# untitled.net
KiCad netlist of a schematic drawn in EAGLE
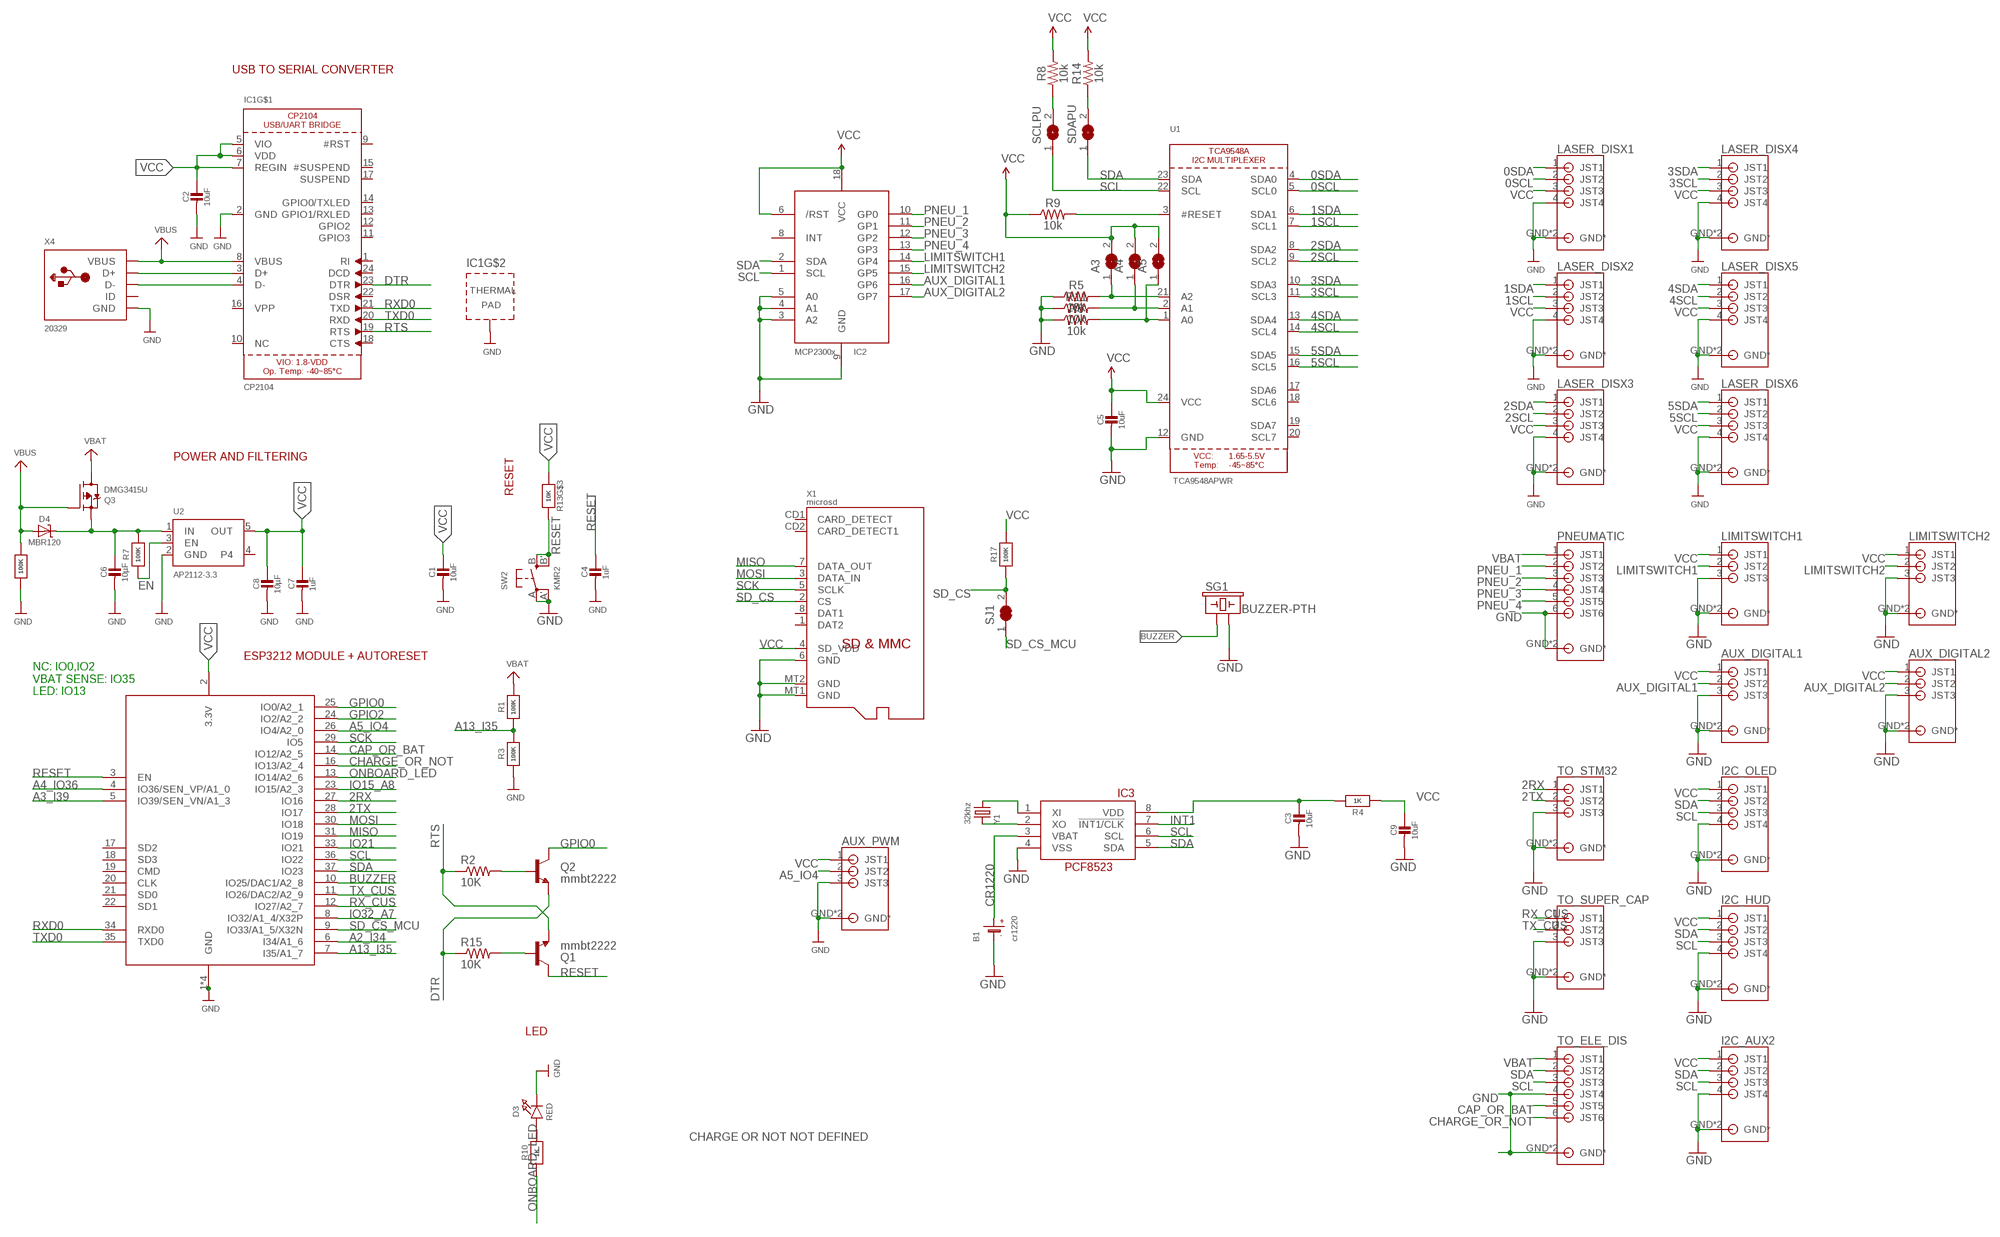
[diagram p0: schematic, sheet 1]

(export (version "E")
  (design (tool "Eeschema 10.0.6"))
  (components
    (comp (ref "A3")
      (value "SOLDERJUMPER")
      (footprint "eagle-import:SOLDERJUMPER_ARROW_NOPASTE")
      (libsource (lib "eagle-import") (part "SOLDERJUMPER"))
    )
    (comp (ref "A4")
      (value "SOLDERJUMPER")
      (footprint "eagle-import:SOLDERJUMPER_ARROW_NOPASTE")
      (libsource (lib "eagle-import") (part "SOLDERJUMPER"))
    )
    (comp (ref "A5")
      (value "SOLDERJUMPER")
      (footprint "eagle-import:SOLDERJUMPER_ARROW_NOPASTE")
      (libsource (lib "eagle-import") (part "SOLDERJUMPER"))
    )
    (comp (ref "AUX_DIGITAL1")
      (value "S3B-PH-SM4_TB")
      (footprint "eagle-import:S3B-PH-SM4_TB")
      (libsource (lib "eagle-import") (part "S3B-PH-SM4_TB"))
    )
    (comp (ref "AUX_DIGITAL2")
      (value "S3B-PH-SM4_TB")
      (footprint "eagle-import:S3B-PH-SM4_TB")
      (libsource (lib "eagle-import") (part "S3B-PH-SM4_TB"))
    )
    (comp (ref "AUX_PWM")
      (value "S3B-PH-SM4_TB")
      (footprint "eagle-import:S3B-PH-SM4_TB")
      (libsource (lib "eagle-import") (part "S3B-PH-SM4_TB"))
    )
    (comp (ref "B1")
      (value "cr1220")
      (footprint "eagle-import:CR1220-2")
      (libsource (lib "eagle-import") (part "BATTERYCR1220_2"))
    )
    (comp (ref "C1")
      (value "10uF")
      (footprint "eagle-import:0805-NO")
      (libsource (lib "eagle-import") (part "CAP_CERAMIC0805-NOOUTLINE"))
    )
    (comp (ref "C2")
      (value "10uF")
      (footprint "eagle-import:0805-NO")
      (libsource (lib "eagle-import") (part "CAP_CERAMIC0805-NOOUTLINE"))
    )
    (comp (ref "C3")
      (value "10uF")
      (footprint "eagle-import:0805-NO")
      (libsource (lib "eagle-import") (part "CAP_CERAMIC0805-NOOUTLINE"))
    )
    (comp (ref "C4")
      (value "1uF")
      (footprint "eagle-import:0603-NO")
      (libsource (lib "eagle-import") (part "CAP_CERAMIC0603_NO"))
    )
    (comp (ref "C5")
      (value "10uF")
      (footprint "eagle-import:0805-NO")
      (libsource (lib "eagle-import") (part "CAP_CERAMIC0805-NOOUTLINE"))
    )
    (comp (ref "C6")
      (value "10µF")
      (footprint "eagle-import:0805-NO")
      (libsource (lib "eagle-import") (part "CAP_CERAMIC0805-NOOUTLINE"))
    )
    (comp (ref "C7")
      (value "1uF")
      (footprint "eagle-import:0603-NO")
      (libsource (lib "eagle-import") (part "CAP_CERAMIC0603_NO"))
    )
    (comp (ref "C8")
      (value "10µF")
      (footprint "eagle-import:0805-NO")
      (libsource (lib "eagle-import") (part "CAP_CERAMIC0805-NOOUTLINE"))
    )
    (comp (ref "C9")
      (value "10uF")
      (footprint "eagle-import:0805-NO")
      (libsource (lib "eagle-import") (part "CAP_CERAMIC0805-NOOUTLINE"))
    )
    (comp (ref "D3")
      (value "RED")
      (footprint "eagle-import:CHIPLED_0805_NOOUTLINE")
      (libsource (lib "eagle-import") (part "LED0805_NOOUTLINE"))
    )
    (comp (ref "D4")
      (value "MBR120")
      (footprint "eagle-import:SOD-123")
      (libsource (lib "eagle-import") (part "DIODE-SCHOTTKYSOD-123"))
    )
    (comp (ref "I2C_AUX2")
      (value "S4B-PH-SM4_TB")
      (footprint "eagle-import:S4B-PH-SM4_TB")
      (libsource (lib "eagle-import") (part "NewKevinMade_S4B-PH-SM4_TB"))
    )
    (comp (ref "I2C_HUD")
      (value "S4B-PH-SM4_TB")
      (footprint "eagle-import:S4B-PH-SM4_TB")
      (libsource (lib "eagle-import") (part "NewKevinMade_S4B-PH-SM4_TB"))
    )
    (comp (ref "I2C_OLED")
      (value "S4B-PH-SM4_TB")
      (footprint "eagle-import:S4B-PH-SM4_TB")
      (libsource (lib "eagle-import") (part "NewKevinMade_S4B-PH-SM4_TB"))
    )
    (comp (ref "IC1")
      (value "CP2104")
      (footprint "eagle-import:QFN24_4MM_SMSC")
      (libsource (lib "eagle-import") (part "CP2104"))
    )
    (comp (ref "IC2")
      (value "MCP23008/SO")
      (footprint "eagle-import:SO18W")
      (libsource (lib "eagle-import") (part "MCP23008/SO"))
    )
    (comp (ref "IC3")
      (value "PCF8523T")
      (footprint "eagle-import:SOIC8_150MIL")
      (libsource (lib "eagle-import") (part "RTC_PCF8523T"))
    )
    (comp (ref "LASER_DISX1")
      (value "S4B-PH-SM4_TB")
      (footprint "eagle-import:S4B-PH-SM4_TB")
      (libsource (lib "eagle-import") (part "S4B-PH-SM4_TB"))
    )
    (comp (ref "LASER_DISX2")
      (value "S4B-PH-SM4_TB")
      (footprint "eagle-import:S4B-PH-SM4_TB")
      (libsource (lib "eagle-import") (part "S4B-PH-SM4_TB"))
    )
    (comp (ref "LASER_DISX3")
      (value "S4B-PH-SM4_TB")
      (footprint "eagle-import:S4B-PH-SM4_TB")
      (libsource (lib "eagle-import") (part "S4B-PH-SM4_TB"))
    )
    (comp (ref "LASER_DISX4")
      (value "S4B-PH-SM4_TB")
      (footprint "eagle-import:S4B-PH-SM4_TB")
      (libsource (lib "eagle-import") (part "S4B-PH-SM4_TB"))
    )
    (comp (ref "LASER_DISX5")
      (value "S4B-PH-SM4_TB")
      (footprint "eagle-import:S4B-PH-SM4_TB")
      (libsource (lib "eagle-import") (part "S4B-PH-SM4_TB"))
    )
    (comp (ref "LASER_DISX6")
      (value "S4B-PH-SM4_TB")
      (footprint "eagle-import:S4B-PH-SM4_TB")
      (libsource (lib "eagle-import") (part "S4B-PH-SM4_TB"))
    )
    (comp (ref "LIMITSWITCH1")
      (value "S3B-PH-SM4_TB")
      (footprint "eagle-import:S3B-PH-SM4_TB")
      (libsource (lib "eagle-import") (part "S3B-PH-SM4_TB"))
    )
    (comp (ref "LIMITSWITCH2")
      (value "S3B-PH-SM4_TB")
      (footprint "eagle-import:S3B-PH-SM4_TB")
      (libsource (lib "eagle-import") (part "S3B-PH-SM4_TB"))
    )
    (comp (ref "PNEUMATIC")
      (value "S6B-PH-SM4_TB")
      (footprint "eagle-import:S6B-PH-SM4_TB")
      (libsource (lib "eagle-import") (part "S6B-PH-SM4_TB"))
    )
    (comp (ref "Q1")
      (value "mmbt2222")
      (footprint "eagle-import:SOT23-3")
      (libsource (lib "eagle-import") (part "TRANSISTOR_NPNSOT23-3"))
    )
    (comp (ref "Q2")
      (value "mmbt2222")
      (footprint "eagle-import:SOT23-3")
      (libsource (lib "eagle-import") (part "TRANSISTOR_NPNSOT23-3"))
    )
    (comp (ref "Q3")
      (value "DMG3415U")
      (footprint "eagle-import:SOT23-R")
      (libsource (lib "eagle-import") (part "MOSFET-P"))
    )
    (comp (ref "R1")
      (value "100K")
      (footprint "eagle-import:0603-NO")
      (libsource (lib "eagle-import") (part "RESISTOR_0603_NOOUT"))
    )
    (comp (ref "R2")
      (value "10K")
      (footprint "eagle-import:0603-RES")
      (libsource (lib "eagle-import") (part "10KOHM-1/10W-1%(0603)0603"))
    )
    (comp (ref "R3")
      (value "100K")
      (footprint "eagle-import:0603-NO")
      (libsource (lib "eagle-import") (part "RESISTOR_0603_NOOUT"))
    )
    (comp (ref "R4")
      (value "1K")
      (footprint "eagle-import:0603-NO")
      (libsource (lib "eagle-import") (part "RESISTOR_0603_NOOUT"))
    )
    (comp (ref "R5")
      (value "10k")
      (footprint "eagle-import:0603")
      (libsource (lib "eagle-import") (part "10KOHM-0603-1/10W-1%"))
    )
    (comp (ref "R6")
      (value "10k")
      (footprint "eagle-import:0603")
      (libsource (lib "eagle-import") (part "10KOHM-0603-1/10W-1%"))
    )
    (comp (ref "R7")
      (value "100K")
      (footprint "eagle-import:0603-NO")
      (libsource (lib "eagle-import") (part "RESISTOR_0603_NOOUT"))
    )
    (comp (ref "R8")
      (value "10k")
      (footprint "eagle-import:0603")
      (libsource (lib "eagle-import") (part "10KOHM-0603-1/10W-1%"))
    )
    (comp (ref "R9")
      (value "10k")
      (footprint "eagle-import:0603")
      (libsource (lib "eagle-import") (part "10KOHM-0603-1/10W-1%"))
    )
    (comp (ref "R10")
      (value "1K")
      (footprint "eagle-import:0603-NO")
      (libsource (lib "eagle-import") (part "RESISTOR_0603_NOOUT"))
    )
    (comp (ref "R11")
      (value "10k")
      (footprint "eagle-import:0603")
      (libsource (lib "eagle-import") (part "10KOHM-0603-1/10W-1%"))
    )
    (comp (ref "R12")
      (value "100K")
      (footprint "eagle-import:0603-NO")
      (libsource (lib "eagle-import") (part "RESISTOR_0603_NOOUT"))
    )
    (comp (ref "R13")
      (value "10K")
      (footprint "eagle-import:RESPACK_4X0603")
      (libsource (lib "eagle-import") (part "RESISTOR_4PACK"))
    )
    (comp (ref "R14")
      (value "10k")
      (footprint "eagle-import:0603")
      (libsource (lib "eagle-import") (part "10KOHM-0603-1/10W-1%"))
    )
    (comp (ref "R15")
      (value "10K")
      (footprint "eagle-import:0603-RES")
      (libsource (lib "eagle-import") (part "10KOHM-1/10W-1%(0603)0603"))
    )
    (comp (ref "R17")
      (value "100K")
      (footprint "eagle-import:0603-NO")
      (libsource (lib "eagle-import") (part "RESISTOR_0603_NOOUT"))
    )
    (comp (ref "SCLPU")
      (value "SOLDERJUMPERCLOSED")
      (footprint "eagle-import:SOLDERJUMPER_CLOSEDWIRE")
      (libsource (lib "eagle-import") (part "SOLDERJUMPERCLOSED"))
    )
    (comp (ref "SDAPU")
      (value "SOLDERJUMPERCLOSED")
      (footprint "eagle-import:SOLDERJUMPER_CLOSEDWIRE")
      (libsource (lib "eagle-import") (part "SOLDERJUMPERCLOSED"))
    )
    (comp (ref "SG1")
      (value "BUZZER-PTH")
      (footprint "eagle-import:BUZZER-12MM")
      (libsource (lib "eagle-import") (part "BUZZER-PTH"))
    )
    (comp (ref "SJ1")
      (value "SOLDERJUMPER_CLOSED")
      (footprint "eagle-import:SOLDERJUMPER_CLOSEDWIRE")
      (libsource (lib "eagle-import") (part "SOLDERJUMPER_CLOSED"))
    )
    (comp (ref "SW2")
      (value "KMR2")
      (footprint "eagle-import:BTN_KMR2_4.6X2.8")
      (libsource (lib "eagle-import") (part "SWITCH_TACT_SMT4.6X2.8"))
    )
    (comp (ref "TO_ELE_DIS")
      (value "S6B-PH-SM4_TB")
      (footprint "eagle-import:S6B-PH-SM4_TB")
      (libsource (lib "eagle-import") (part "S6B-PH-SM4_TB"))
    )
    (comp (ref "TO_STM32")
      (value "S3B-PH-SM4_TB")
      (footprint "eagle-import:S3B-PH-SM4_TB")
      (libsource (lib "eagle-import") (part "S3B-PH-SM4_TB"))
    )
    (comp (ref "TO_SUPER_CAP")
      (value "S3B-PH-SM4_TB")
      (footprint "eagle-import:S3B-PH-SM4_TB")
      (libsource (lib "eagle-import") (part "S3B-PH-SM4_TB"))
    )
    (comp (ref "U1")
      (value "TCA9548APWR")
      (footprint "eagle-import:TSSOP24")
      (libsource (lib "eagle-import") (part "TCA9548A"))
    )
    (comp (ref "U2")
      (value "AP2112-3.3")
      (footprint "eagle-import:SOT23-5")
      (libsource (lib "eagle-import") (part "VREG_SOT23-5"))
    )
    (comp (ref "X1")
      (value "microsd")
      (footprint "eagle-import:MICROSD")
      (libsource (lib "eagle-import") (part "MICROSD"))
    )
    (comp (ref "X2")
      (value "ESP32_WROOM32_SKINNY")
      (footprint "eagle-import:WROOM32_SKINNY")
      (libsource (lib "eagle-import") (part "ESP32_WROOM32_SKINNY"))
    )
    (comp (ref "X4")
      (value "20329")
      (footprint "eagle-import:4UCONN_20329_V2")
      (libsource (lib "eagle-import") (part "USB_MICRO_20329_V2"))
    )
    (comp (ref "Y1")
      (value "32khz")
      (footprint "eagle-import:CRYSTAL_8X3.8")
      (libsource (lib "eagle-import") (part "CRYSTAL8.0X3.8"))
    )
  )
  (nets
    (net (code "1") (name "/0SCL") (class "Default")
      (node (ref "LASER_DISX1") (pin "2") (pinfunction "JST2_2") (pintype "bidirectional"))
      (node (ref "U1") (pin "5") (pinfunction "SCL0_5") (pintype "bidirectional"))
    )
    (net (code "2") (name "/0SDA") (class "Default")
      (node (ref "LASER_DISX1") (pin "1") (pinfunction "JST1_1") (pintype "bidirectional"))
      (node (ref "U1") (pin "4") (pinfunction "SDA0_4") (pintype "bidirectional"))
    )
    (net (code "3") (name "/1SCL") (class "Default")
      (node (ref "LASER_DISX2") (pin "2") (pinfunction "JST2_2") (pintype "bidirectional"))
      (node (ref "U1") (pin "7") (pinfunction "SCL1_7") (pintype "bidirectional"))
    )
    (net (code "4") (name "/1SDA") (class "Default")
      (node (ref "LASER_DISX2") (pin "1") (pinfunction "JST1_1") (pintype "bidirectional"))
      (node (ref "U1") (pin "6") (pinfunction "SDA1_6") (pintype "bidirectional"))
    )
    (net (code "5") (name "/2RX") (class "Default")
      (node (ref "TO_STM32") (pin "1") (pinfunction "JST1_1") (pintype "bidirectional"))
      (node (ref "X2") (pin "27") (pinfunction "IO16_27") (pintype "bidirectional"))
    )
    (net (code "6") (name "/2SCL") (class "Default")
      (node (ref "LASER_DISX3") (pin "2") (pinfunction "JST2_2") (pintype "bidirectional"))
      (node (ref "U1") (pin "9") (pinfunction "SCL2_9") (pintype "bidirectional"))
    )
    (net (code "7") (name "/2SDA") (class "Default")
      (node (ref "LASER_DISX3") (pin "1") (pinfunction "JST1_1") (pintype "bidirectional"))
      (node (ref "U1") (pin "8") (pinfunction "SDA2_8") (pintype "bidirectional"))
    )
    (net (code "8") (name "/2TX") (class "Default")
      (node (ref "TO_STM32") (pin "2") (pinfunction "JST2_2") (pintype "bidirectional"))
      (node (ref "X2") (pin "28") (pinfunction "IO17_28") (pintype "bidirectional"))
    )
    (net (code "9") (name "/3SCL") (class "Default")
      (node (ref "LASER_DISX4") (pin "2") (pinfunction "JST2_2") (pintype "bidirectional"))
      (node (ref "U1") (pin "11") (pinfunction "SCL3_11") (pintype "bidirectional"))
    )
    (net (code "10") (name "/3SDA") (class "Default")
      (node (ref "LASER_DISX4") (pin "1") (pinfunction "JST1_1") (pintype "bidirectional"))
      (node (ref "U1") (pin "10") (pinfunction "SDA3_10") (pintype "bidirectional"))
    )
    (net (code "11") (name "/4SCL") (class "Default")
      (node (ref "LASER_DISX5") (pin "2") (pinfunction "JST2_2") (pintype "bidirectional"))
      (node (ref "U1") (pin "14") (pinfunction "SCL4_14") (pintype "bidirectional"))
    )
    (net (code "12") (name "/4SDA") (class "Default")
      (node (ref "LASER_DISX5") (pin "1") (pinfunction "JST1_1") (pintype "bidirectional"))
      (node (ref "U1") (pin "13") (pinfunction "SDA4_13") (pintype "bidirectional"))
    )
    (net (code "13") (name "/5SCL") (class "Default")
      (node (ref "LASER_DISX6") (pin "2") (pinfunction "JST2_2") (pintype "bidirectional"))
      (node (ref "U1") (pin "16") (pinfunction "SCL5_16") (pintype "bidirectional"))
    )
    (net (code "14") (name "/5SDA") (class "Default")
      (node (ref "LASER_DISX6") (pin "1") (pinfunction "JST1_1") (pintype "bidirectional"))
      (node (ref "U1") (pin "15") (pinfunction "SDA5_15") (pintype "bidirectional"))
    )
    (net (code "15") (name "/A2_I34") (class "Default")
      (node (ref "X2") (pin "6") (pinfunction "I34/A1_6_6") (pintype "bidirectional"))
    )
    (net (code "16") (name "/A3_I39") (class "Default")
      (node (ref "X2") (pin "5") (pinfunction "IO39/SEN_VN/A1_3_5") (pintype "passive"))
    )
    (net (code "17") (name "/A4_IO36") (class "Default")
      (node (ref "X2") (pin "4") (pinfunction "IO36/SEN_VP/A1_0_4") (pintype "passive"))
    )
    (net (code "18") (name "/A5_IO4") (class "Default")
      (node (ref "AUX_PWM") (pin "2") (pinfunction "JST2_2") (pintype "bidirectional"))
      (node (ref "X2") (pin "26") (pinfunction "IO4/A2_0_26") (pintype "bidirectional"))
    )
    (net (code "19") (name "/A13_I35") (class "Default")
      (node (ref "R1") (pin "1") (pinfunction "1_1") (pintype "passive"))
      (node (ref "R3") (pin "2") (pinfunction "2_2") (pintype "passive"))
      (node (ref "X2") (pin "7") (pinfunction "I35/A1_7_7") (pintype "bidirectional"))
    )
    (net (code "20") (name "/AUX_DIGITAL1") (class "Default")
      (node (ref "AUX_DIGITAL1") (pin "2") (pinfunction "JST2_2") (pintype "bidirectional"))
      (node (ref "IC2") (pin "16") (pinfunction "GP6_16") (pintype "bidirectional"))
    )
    (net (code "21") (name "/AUX_DIGITAL2") (class "Default")
      (node (ref "AUX_DIGITAL2") (pin "2") (pinfunction "JST2_2") (pintype "bidirectional"))
      (node (ref "IC2") (pin "17") (pinfunction "GP7_17") (pintype "bidirectional"))
    )
    (net (code "22") (name "/CAP_OR_BAT") (class "Default")
      (node (ref "TO_ELE_DIS") (pin "5") (pinfunction "JST5_5") (pintype "bidirectional"))
      (node (ref "X2") (pin "14") (pinfunction "IO12/A2_5_14") (pintype "bidirectional"))
    )
    (net (code "23") (name "/CHARGE_OR_NOT") (class "Default")
      (node (ref "TO_ELE_DIS") (pin "6") (pinfunction "JST6_6") (pintype "bidirectional"))
      (node (ref "X2") (pin "16") (pinfunction "IO13/A2_4_16") (pintype "bidirectional"))
    )
    (net (code "24") (name "/CR1220") (class "Default")
      (node (ref "B1") (pin "+") (pinfunction "+_+") (pintype "passive"))
      (node (ref "IC3") (pin "3") (pinfunction "VBAT_3") (pintype "power_in"))
    )
    (net (code "25") (name "/DTR") (class "Default")
      (node (ref "IC1") (pin "23") (pinfunction "DTR_23") (pintype "output"))
      (node (ref "Q2") (pin "2") (pinfunction "E_2") (pintype "passive"))
      (node (ref "R15") (pin "1") (pinfunction "1_1") (pintype "passive"))
    )
    (net (code "26") (name "/EN") (class "Default")
      (node (ref "R7") (pin "1") (pinfunction "1_1") (pintype "passive"))
      (node (ref "U2") (pin "3") (pinfunction "EN_3") (pintype "input"))
    )
    (net (code "27") (name "/GPIO0") (class "Default")
      (node (ref "Q2") (pin "3") (pinfunction "C_3") (pintype "passive"))
      (node (ref "X2") (pin "25") (pinfunction "IO0/A2_1_25") (pintype "bidirectional"))
    )
    (net (code "28") (name "/GPIO2") (class "Default")
      (node (ref "X2") (pin "24") (pinfunction "IO2/A2_2_24") (pintype "bidirectional"))
    )
    (net (code "29") (name "/INT1") (class "Default")
      (node (ref "IC3") (pin "7") (pinfunction "~{INT1/CLK}_7") (pintype "output"))
    )
    (net (code "30") (name "/IO15_A8") (class "Default")
      (node (ref "X2") (pin "23") (pinfunction "IO15/A2_3_23") (pintype "bidirectional"))
    )
    (net (code "31") (name "/IO21") (class "Default")
      (node (ref "X2") (pin "33") (pinfunction "IO21_33") (pintype "bidirectional"))
    )
    (net (code "32") (name "/IO32_A7") (class "Default")
      (node (ref "X2") (pin "8") (pinfunction "IO32/A1_4/X32P_8") (pintype "bidirectional"))
    )
    (net (code "33") (name "/LIMITSWITCH1") (class "Default")
      (node (ref "IC2") (pin "14") (pinfunction "GP4_14") (pintype "bidirectional"))
      (node (ref "LIMITSWITCH1") (pin "2") (pinfunction "JST2_2") (pintype "bidirectional"))
    )
    (net (code "34") (name "/LIMITSWITCH2") (class "Default")
      (node (ref "IC2") (pin "15") (pinfunction "GP5_15") (pintype "bidirectional"))
      (node (ref "LIMITSWITCH2") (pin "2") (pinfunction "JST2_2") (pintype "bidirectional"))
    )
    (net (code "35") (name "/MISO") (class "Default")
      (node (ref "X1") (pin "7") (pinfunction "DATA_OUT_7") (pintype "output"))
      (node (ref "X2") (pin "31") (pinfunction "IO19_31") (pintype "bidirectional"))
    )
    (net (code "36") (name "/MOSI") (class "Default")
      (node (ref "X1") (pin "3") (pinfunction "DATA_IN_3") (pintype "input"))
      (node (ref "X2") (pin "30") (pinfunction "IO18_30") (pintype "bidirectional"))
    )
    (net (code "37") (name "/ONBOARD_LED") (class "Default")
      (node (ref "R10") (pin "1") (pinfunction "1_1") (pintype "passive"))
      (node (ref "X2") (pin "13") (pinfunction "IO14/A2_6_13") (pintype "bidirectional"))
    )
    (net (code "38") (name "/PNEU_1") (class "Default")
      (node (ref "IC2") (pin "10") (pinfunction "GP0_10") (pintype "bidirectional"))
      (node (ref "PNEUMATIC") (pin "2") (pinfunction "JST2_2") (pintype "bidirectional"))
    )
    (net (code "39") (name "/PNEU_2") (class "Default")
      (node (ref "IC2") (pin "11") (pinfunction "GP1_11") (pintype "bidirectional"))
      (node (ref "PNEUMATIC") (pin "3") (pinfunction "JST3_3") (pintype "bidirectional"))
    )
    (net (code "40") (name "/PNEU_3") (class "Default")
      (node (ref "IC2") (pin "12") (pinfunction "GP2_12") (pintype "bidirectional"))
      (node (ref "PNEUMATIC") (pin "4") (pinfunction "JST4_4") (pintype "bidirectional"))
    )
    (net (code "41") (name "/PNEU_4") (class "Default")
      (node (ref "IC2") (pin "13") (pinfunction "GP3_13") (pintype "bidirectional"))
      (node (ref "PNEUMATIC") (pin "5") (pinfunction "JST5_5") (pintype "bidirectional"))
    )
    (net (code "42") (name "/RESET") (class "Default")
      (node (ref "C4") (pin "1") (pinfunction "1_1") (pintype "passive"))
      (node (ref "Q1") (pin "3") (pinfunction "C_3") (pintype "passive"))
      (node (ref "R13") (pin "6") (pinfunction "2_6") (pintype "passive"))
      (node (ref "SW2") (pin "B") (pinfunction "S_B") (pintype "passive"))
      (node (ref "SW2") (pin "B'") (pinfunction "S1_B'") (pintype "passive"))
      (node (ref "X2") (pin "3") (pinfunction "EN_3") (pintype "input"))
    )
    (net (code "43") (name "/RTS") (class "Default")
      (node (ref "IC1") (pin "19") (pinfunction "RTS_19") (pintype "output"))
      (node (ref "Q1") (pin "2") (pinfunction "E_2") (pintype "passive"))
      (node (ref "R2") (pin "1") (pinfunction "1_1") (pintype "passive"))
    )
    (net (code "44") (name "/RXD0") (class "Default")
      (node (ref "IC1") (pin "21") (pinfunction "TXD_21") (pintype "output"))
      (node (ref "X2") (pin "34") (pinfunction "RXD0_34") (pintype "input"))
    )
    (net (code "45") (name "/RX_CUS") (class "Default")
      (node (ref "TO_SUPER_CAP") (pin "1") (pinfunction "JST1_1") (pintype "bidirectional"))
      (node (ref "X2") (pin "12") (pinfunction "IO27/A2_7_12") (pintype "bidirectional"))
    )
    (net (code "46") (name "/SCK") (class "Default")
      (node (ref "X1") (pin "5") (pinfunction "SCLK_5") (pintype "input"))
      (node (ref "X2") (pin "29") (pinfunction "IO5_29") (pintype "bidirectional"))
    )
    (net (code "47") (name "/SCL") (class "Default")
      (node (ref "I2C_AUX2") (pin "3") (pinfunction "JST3_3") (pintype "bidirectional"))
      (node (ref "I2C_HUD") (pin "3") (pinfunction "JST3_3") (pintype "bidirectional"))
      (node (ref "I2C_OLED") (pin "3") (pinfunction "JST3_3") (pintype "bidirectional"))
      (node (ref "IC2") (pin "1") (pinfunction "SCL_1") (pintype "bidirectional"))
      (node (ref "IC3") (pin "6") (pinfunction "SCL_6") (pintype "bidirectional"))
      (node (ref "SCLPU") (pin "1") (pinfunction "1_1") (pintype "passive"))
      (node (ref "TO_ELE_DIS") (pin "3") (pinfunction "JST3_3") (pintype "bidirectional"))
      (node (ref "U1") (pin "22") (pinfunction "SCL_22") (pintype "bidirectional"))
      (node (ref "X2") (pin "36") (pinfunction "IO22_36") (pintype "bidirectional"))
    )
    (net (code "48") (name "/SDA") (class "Default")
      (node (ref "I2C_AUX2") (pin "2") (pinfunction "JST2_2") (pintype "bidirectional"))
      (node (ref "I2C_HUD") (pin "2") (pinfunction "JST2_2") (pintype "bidirectional"))
      (node (ref "I2C_OLED") (pin "2") (pinfunction "JST2_2") (pintype "bidirectional"))
      (node (ref "IC2") (pin "2") (pinfunction "SDA_2") (pintype "bidirectional"))
      (node (ref "IC3") (pin "5") (pinfunction "SDA_5") (pintype "bidirectional"))
      (node (ref "SDAPU") (pin "1") (pinfunction "1_1") (pintype "passive"))
      (node (ref "TO_ELE_DIS") (pin "2") (pinfunction "JST2_2") (pintype "bidirectional"))
      (node (ref "U1") (pin "23") (pinfunction "SDA_23") (pintype "bidirectional"))
      (node (ref "X2") (pin "37") (pinfunction "IO23_37") (pintype "bidirectional"))
    )
    (net (code "49") (name "/SD_CS") (class "Default")
      (node (ref "R17") (pin "1") (pinfunction "1_1") (pintype "passive"))
      (node (ref "SJ1") (pin "2") (pinfunction "2_2") (pintype "passive"))
      (node (ref "X1") (pin "2") (pinfunction "CS_2") (pintype "input"))
    )
    (net (code "50") (name "/SD_CS_MCU") (class "Default")
      (node (ref "SJ1") (pin "1") (pinfunction "1_1") (pintype "passive"))
      (node (ref "X2") (pin "9") (pinfunction "IO33/A1_5/X32N_9") (pintype "bidirectional"))
    )
    (net (code "51") (name "/TXD0") (class "Default")
      (node (ref "IC1") (pin "20") (pinfunction "RXD_20") (pintype "input"))
      (node (ref "X2") (pin "35") (pinfunction "TXD0_35") (pintype "output"))
    )
    (net (code "52") (name "/TX_CUS") (class "Default")
      (node (ref "TO_SUPER_CAP") (pin "2") (pinfunction "JST2_2") (pintype "bidirectional"))
      (node (ref "X2") (pin "11") (pinfunction "IO26/DAC2/A2_9_11") (pintype "bidirectional"))
    )
    (net (code "53") (name "BUZZER") (class "Default")
      (node (ref "SG1") (pin "+") (pinfunction "1_+") (pintype "passive"))
      (node (ref "X2") (pin "10") (pinfunction "IO25/DAC1/A2_8_10") (pintype "bidirectional"))
    )
    (net (code "54") (name "GND") (class "Default")
      (node (ref "AUX_DIGITAL1") (pin "3") (pinfunction "JST3_3") (pintype "bidirectional"))
      (node (ref "AUX_DIGITAL1") (pin "GND") (pinfunction "GND*_GND") (pintype "bidirectional"))
      (node (ref "AUX_DIGITAL1") (pin "GND2") (pinfunction "GND*_GND2") (pintype "bidirectional"))
      (node (ref "AUX_DIGITAL2") (pin "3") (pinfunction "JST3_3") (pintype "bidirectional"))
      (node (ref "AUX_DIGITAL2") (pin "GND") (pinfunction "GND*_GND") (pintype "bidirectional"))
      (node (ref "AUX_DIGITAL2") (pin "GND2") (pinfunction "GND*_GND2") (pintype "bidirectional"))
      (node (ref "AUX_PWM") (pin "3") (pinfunction "JST3_3") (pintype "bidirectional"))
      (node (ref "AUX_PWM") (pin "GND") (pinfunction "GND*_GND") (pintype "bidirectional"))
      (node (ref "AUX_PWM") (pin "GND2") (pinfunction "GND*_GND2") (pintype "bidirectional"))
      (node (ref "B1") (pin "-") (pinfunction "-_-") (pintype "passive"))
      (node (ref "C1") (pin "2") (pinfunction "2_2") (pintype "passive"))
      (node (ref "C2") (pin "2") (pinfunction "2_2") (pintype "passive"))
      (node (ref "C3") (pin "2") (pinfunction "2_2") (pintype "passive"))
      (node (ref "C4") (pin "2") (pinfunction "2_2") (pintype "passive"))
      (node (ref "C5") (pin "2") (pinfunction "2_2") (pintype "passive"))
      (node (ref "C6") (pin "2") (pinfunction "2_2") (pintype "passive"))
      (node (ref "C7") (pin "2") (pinfunction "2_2") (pintype "passive"))
      (node (ref "C8") (pin "2") (pinfunction "2_2") (pintype "passive"))
      (node (ref "C9") (pin "2") (pinfunction "2_2") (pintype "passive"))
      (node (ref "D3") (pin "C") (pinfunction "C_C") (pintype "passive"))
      (node (ref "I2C_AUX2") (pin "4") (pinfunction "JST4_4") (pintype "bidirectional"))
      (node (ref "I2C_AUX2") (pin "GND") (pinfunction "GND*_GND") (pintype "bidirectional"))
      (node (ref "I2C_AUX2") (pin "GND2") (pinfunction "GND*_GND2") (pintype "bidirectional"))
      (node (ref "I2C_HUD") (pin "4") (pinfunction "JST4_4") (pintype "bidirectional"))
      (node (ref "I2C_HUD") (pin "GND") (pinfunction "GND*_GND") (pintype "bidirectional"))
      (node (ref "I2C_HUD") (pin "GND2") (pinfunction "GND*_GND2") (pintype "bidirectional"))
      (node (ref "I2C_OLED") (pin "4") (pinfunction "JST4_4") (pintype "bidirectional"))
      (node (ref "I2C_OLED") (pin "GND") (pinfunction "GND*_GND") (pintype "bidirectional"))
      (node (ref "I2C_OLED") (pin "GND2") (pinfunction "GND*_GND2") (pintype "bidirectional"))
      (node (ref "IC1") (pin "2") (pinfunction "GND_2") (pintype "power_in"))
      (node (ref "IC1") (pin "THERM") (pinfunction "TP_THERM") (pintype "power_in"))
      (node (ref "IC2") (pin "3") (pinfunction "A2_3") (pintype "input"))
      (node (ref "IC2") (pin "4") (pinfunction "A1_4") (pintype "input"))
      (node (ref "IC2") (pin "5") (pinfunction "A0_5") (pintype "input"))
      (node (ref "IC2") (pin "9") (pinfunction "GND_9") (pintype "power_in"))
      (node (ref "IC3") (pin "4") (pinfunction "VSS_4") (pintype "power_in"))
      (node (ref "LASER_DISX1") (pin "4") (pinfunction "JST4_4") (pintype "bidirectional"))
      (node (ref "LASER_DISX1") (pin "GND") (pinfunction "GND*_GND") (pintype "bidirectional"))
      (node (ref "LASER_DISX1") (pin "GND2") (pinfunction "GND*_GND2") (pintype "bidirectional"))
      (node (ref "LASER_DISX2") (pin "4") (pinfunction "JST4_4") (pintype "bidirectional"))
      (node (ref "LASER_DISX2") (pin "GND") (pinfunction "GND*_GND") (pintype "bidirectional"))
      (node (ref "LASER_DISX2") (pin "GND2") (pinfunction "GND*_GND2") (pintype "bidirectional"))
      (node (ref "LASER_DISX3") (pin "4") (pinfunction "JST4_4") (pintype "bidirectional"))
      (node (ref "LASER_DISX3") (pin "GND") (pinfunction "GND*_GND") (pintype "bidirectional"))
      (node (ref "LASER_DISX3") (pin "GND2") (pinfunction "GND*_GND2") (pintype "bidirectional"))
      (node (ref "LASER_DISX4") (pin "4") (pinfunction "JST4_4") (pintype "bidirectional"))
      (node (ref "LASER_DISX4") (pin "GND") (pinfunction "GND*_GND") (pintype "bidirectional"))
      (node (ref "LASER_DISX4") (pin "GND2") (pinfunction "GND*_GND2") (pintype "bidirectional"))
      (node (ref "LASER_DISX5") (pin "4") (pinfunction "JST4_4") (pintype "bidirectional"))
      (node (ref "LASER_DISX5") (pin "GND") (pinfunction "GND*_GND") (pintype "bidirectional"))
      (node (ref "LASER_DISX5") (pin "GND2") (pinfunction "GND*_GND2") (pintype "bidirectional"))
      (node (ref "LASER_DISX6") (pin "4") (pinfunction "JST4_4") (pintype "bidirectional"))
      (node (ref "LASER_DISX6") (pin "GND") (pinfunction "GND*_GND") (pintype "bidirectional"))
      (node (ref "LASER_DISX6") (pin "GND2") (pinfunction "GND*_GND2") (pintype "bidirectional"))
      (node (ref "LIMITSWITCH1") (pin "3") (pinfunction "JST3_3") (pintype "bidirectional"))
      (node (ref "LIMITSWITCH1") (pin "GND") (pinfunction "GND*_GND") (pintype "bidirectional"))
      (node (ref "LIMITSWITCH1") (pin "GND2") (pinfunction "GND*_GND2") (pintype "bidirectional"))
      (node (ref "LIMITSWITCH2") (pin "3") (pinfunction "JST3_3") (pintype "bidirectional"))
      (node (ref "LIMITSWITCH2") (pin "GND") (pinfunction "GND*_GND") (pintype "bidirectional"))
      (node (ref "LIMITSWITCH2") (pin "GND2") (pinfunction "GND*_GND2") (pintype "bidirectional"))
      (node (ref "PNEUMATIC") (pin "6") (pinfunction "JST6_6") (pintype "bidirectional"))
      (node (ref "PNEUMATIC") (pin "GND") (pinfunction "GND*_GND") (pintype "bidirectional"))
      (node (ref "PNEUMATIC") (pin "GND2") (pinfunction "GND*_GND2") (pintype "bidirectional"))
      (node (ref "R11") (pin "1") (pinfunction "1_1") (pintype "passive"))
      (node (ref "R12") (pin "1") (pinfunction "1_1") (pintype "passive"))
      (node (ref "R3") (pin "1") (pinfunction "1_1") (pintype "passive"))
      (node (ref "R5") (pin "1") (pinfunction "1_1") (pintype "passive"))
      (node (ref "R6") (pin "1") (pinfunction "1_1") (pintype "passive"))
      (node (ref "SG1") (pin "-") (pinfunction "2_-") (pintype "passive"))
      (node (ref "SW2") (pin "A") (pinfunction "P_A") (pintype "passive"))
      (node (ref "SW2") (pin "A'") (pinfunction "P1_A'") (pintype "passive"))
      (node (ref "TO_ELE_DIS") (pin "4") (pinfunction "JST4_4") (pintype "bidirectional"))
      (node (ref "TO_ELE_DIS") (pin "GND") (pinfunction "GND*_GND") (pintype "bidirectional"))
      (node (ref "TO_ELE_DIS") (pin "GND2") (pinfunction "GND*_GND2") (pintype "bidirectional"))
      (node (ref "TO_STM32") (pin "3") (pinfunction "JST3_3") (pintype "bidirectional"))
      (node (ref "TO_STM32") (pin "GND") (pinfunction "GND*_GND") (pintype "bidirectional"))
      (node (ref "TO_STM32") (pin "GND2") (pinfunction "GND*_GND2") (pintype "bidirectional"))
      (node (ref "TO_SUPER_CAP") (pin "3") (pinfunction "JST3_3") (pintype "bidirectional"))
      (node (ref "TO_SUPER_CAP") (pin "GND") (pinfunction "GND*_GND") (pintype "bidirectional"))
      (node (ref "TO_SUPER_CAP") (pin "GND2") (pinfunction "GND*_GND2") (pintype "bidirectional"))
      (node (ref "U1") (pin "12") (pinfunction "GND_12") (pintype "bidirectional"))
      (node (ref "U2") (pin "2") (pinfunction "GND_2") (pintype "power_in"))
      (node (ref "X1") (pin "6") (pinfunction "GND_6") (pintype "power_in"))
      (node (ref "X1") (pin "MT1") (pinfunction "GND_MT1") (pintype "power_in"))
      (node (ref "X1") (pin "MT2") (pinfunction "GND_MT2") (pintype "power_in"))
      (node (ref "X2") (pin "1") (pinfunction "GND_1") (pintype "passive"))
      (node (ref "X2") (pin "15") (pinfunction "GND_15") (pintype "passive"))
      (node (ref "X2") (pin "38") (pinfunction "GND_38") (pintype "passive"))
      (node (ref "X2") (pin "P$1") (pinfunction "GND_P$1") (pintype "passive"))
      (node (ref "X4") (pin "BASE@1") (pinfunction "GND_BASE@1") (pintype "power_in"))
      (node (ref "X4") (pin "BASE@2") (pinfunction "GND_BASE@2") (pintype "power_in"))
      (node (ref "X4") (pin "GND") (pinfunction "GND_GND") (pintype "power_in"))
      (node (ref "X4") (pin "SPRT@1") (pinfunction "GND_SPRT@1") (pintype "power_in"))
      (node (ref "X4") (pin "SPRT@2") (pinfunction "GND_SPRT@2") (pintype "power_in"))
      (node (ref "X4") (pin "SPRT@3") (pinfunction "GND_SPRT@3") (pintype "power_in"))
      (node (ref "X4") (pin "SPRT@4") (pinfunction "GND_SPRT@4") (pintype "power_in"))
    )
    (net (code "55") (name "Net-(D3-PadA)") (class "Default")
      (node (ref "D3") (pin "A") (pinfunction "A_A") (pintype "passive"))
      (node (ref "R10") (pin "2") (pinfunction "2_2") (pintype "passive"))
    )
    (net (code "56") (name "Net-(IC1A-D+)") (class "Default")
      (node (ref "IC1") (pin "3") (pinfunction "D+_3") (pintype "bidirectional"))
      (node (ref "X4") (pin "D+") (pinfunction "D+_D+") (pintype "bidirectional"))
    )
    (net (code "57") (name "Net-(IC1A-D-)") (class "Default")
      (node (ref "IC1") (pin "4") (pinfunction "D-_4") (pintype "bidirectional"))
      (node (ref "X4") (pin "D-") (pinfunction "D-_D-") (pintype "bidirectional"))
    )
    (net (code "58") (name "Net-(IC3-VDD)") (class "Default")
      (node (ref "C3") (pin "1") (pinfunction "1_1") (pintype "passive"))
      (node (ref "IC3") (pin "8") (pinfunction "VDD_8") (pintype "power_in"))
      (node (ref "R4") (pin "2") (pinfunction "2_2") (pintype "passive"))
    )
    (net (code "59") (name "Net-(IC3-XI)") (class "Default")
      (node (ref "IC3") (pin "1") (pinfunction "XI_1") (pintype "input"))
      (node (ref "Y1") (pin "P$4") (pinfunction "2_P$4") (pintype "passive"))
    )
    (net (code "60") (name "Net-(IC3-XO)") (class "Default")
      (node (ref "IC3") (pin "2") (pinfunction "XO_2") (pintype "output"))
      (node (ref "Y1") (pin "P$1") (pinfunction "1_P$1") (pintype "passive"))
    )
    (net (code "61") (name "Net-(Q1-B)") (class "Default")
      (node (ref "Q1") (pin "1") (pinfunction "B_1") (pintype "passive"))
      (node (ref "R15") (pin "2") (pinfunction "2_2") (pintype "passive"))
    )
    (net (code "62") (name "Net-(Q2-B)") (class "Default")
      (node (ref "Q2") (pin "1") (pinfunction "B_1") (pintype "passive"))
      (node (ref "R2") (pin "2") (pinfunction "2_2") (pintype "passive"))
    )
    (net (code "63") (name "Net-(Q3-S)") (class "Default")
      (node (ref "C6") (pin "1") (pinfunction "1_1") (pintype "passive"))
      (node (ref "D4") (pin "C") (pinfunction "C_C") (pintype "passive"))
      (node (ref "Q3") (pin "2") (pinfunction "S_2") (pintype "passive"))
      (node (ref "R7") (pin "2") (pinfunction "2_2") (pintype "passive"))
      (node (ref "U2") (pin "1") (pinfunction "IN_1") (pintype "power_in"))
    )
    (net (code "64") (name "Net-(R8-Pad1)") (class "Default")
      (node (ref "R8") (pin "1") (pinfunction "1_1") (pintype "passive"))
      (node (ref "SCLPU") (pin "2") (pinfunction "2_2") (pintype "passive"))
    )
    (net (code "65") (name "Net-(R14-Pad1)") (class "Default")
      (node (ref "R14") (pin "1") (pinfunction "1_1") (pintype "passive"))
      (node (ref "SDAPU") (pin "2") (pinfunction "2_2") (pintype "passive"))
    )
    (net (code "66") (name "Net-(U1-#RESET)") (class "Default")
      (node (ref "R9") (pin "2") (pinfunction "2_2") (pintype "passive"))
      (node (ref "U1") (pin "3") (pinfunction "#RESET_3") (pintype "bidirectional"))
    )
    (net (code "67") (name "Net-(U1-A0)") (class "Default")
      (node (ref "A5") (pin "1") (pinfunction "1_1") (pintype "passive"))
      (node (ref "R6") (pin "2") (pinfunction "2_2") (pintype "passive"))
      (node (ref "U1") (pin "1") (pinfunction "A0_1") (pintype "bidirectional"))
    )
    (net (code "68") (name "Net-(U1-A1)") (class "Default")
      (node (ref "A4") (pin "1") (pinfunction "1_1") (pintype "passive"))
      (node (ref "R11") (pin "2") (pinfunction "2_2") (pintype "passive"))
      (node (ref "U1") (pin "2") (pinfunction "A1_2") (pintype "bidirectional"))
    )
    (net (code "69") (name "Net-(U1-A2)") (class "Default")
      (node (ref "A3") (pin "1") (pinfunction "1_1") (pintype "passive"))
      (node (ref "R5") (pin "2") (pinfunction "2_2") (pintype "passive"))
      (node (ref "U1") (pin "21") (pinfunction "A2_21") (pintype "bidirectional"))
    )
    (net (code "70") (name "VBAT") (class "Default")
      (node (ref "PNEUMATIC") (pin "1") (pinfunction "JST1_1") (pintype "bidirectional"))
      (node (ref "Q3") (pin "3") (pinfunction "D_3") (pintype "passive"))
      (node (ref "R1") (pin "2") (pinfunction "2_2") (pintype "passive"))
      (node (ref "TO_ELE_DIS") (pin "1") (pinfunction "JST1_1") (pintype "bidirectional"))
    )
    (net (code "71") (name "VBUS") (class "Default")
      (node (ref "D4") (pin "A") (pinfunction "A_A") (pintype "passive"))
      (node (ref "IC1") (pin "8") (pinfunction "VBUS_8") (pintype "power_in"))
      (node (ref "Q3") (pin "1") (pinfunction "G_1") (pintype "passive"))
      (node (ref "R12") (pin "2") (pinfunction "2_2") (pintype "passive"))
      (node (ref "X4") (pin "VBUS") (pinfunction "VBUS_VBUS") (pintype "power_in"))
    )
    (net (code "72") (name "VCC") (class "Default")
      (node (ref "A3") (pin "2") (pinfunction "2_2") (pintype "passive"))
      (node (ref "A4") (pin "2") (pinfunction "2_2") (pintype "passive"))
      (node (ref "A5") (pin "2") (pinfunction "2_2") (pintype "passive"))
      (node (ref "AUX_DIGITAL1") (pin "1") (pinfunction "JST1_1") (pintype "bidirectional"))
      (node (ref "AUX_DIGITAL2") (pin "1") (pinfunction "JST1_1") (pintype "bidirectional"))
      (node (ref "AUX_PWM") (pin "1") (pinfunction "JST1_1") (pintype "bidirectional"))
      (node (ref "C1") (pin "1") (pinfunction "1_1") (pintype "passive"))
      (node (ref "C2") (pin "1") (pinfunction "1_1") (pintype "passive"))
      (node (ref "C5") (pin "1") (pinfunction "1_1") (pintype "passive"))
      (node (ref "C7") (pin "1") (pinfunction "1_1") (pintype "passive"))
      (node (ref "C8") (pin "1") (pinfunction "1_1") (pintype "passive"))
      (node (ref "C9") (pin "1") (pinfunction "1_1") (pintype "passive"))
      (node (ref "I2C_AUX2") (pin "1") (pinfunction "JST1_1") (pintype "bidirectional"))
      (node (ref "I2C_HUD") (pin "1") (pinfunction "JST1_1") (pintype "bidirectional"))
      (node (ref "I2C_OLED") (pin "1") (pinfunction "JST1_1") (pintype "bidirectional"))
      (node (ref "IC1") (pin "5") (pinfunction "VIO_5") (pintype "power_in"))
      (node (ref "IC1") (pin "6") (pinfunction "VDD_6") (pintype "power_in"))
      (node (ref "IC1") (pin "7") (pinfunction "REGIN_7") (pintype "power_in"))
      (node (ref "IC2") (pin "18") (pinfunction "VCC_18") (pintype "power_in"))
      (node (ref "IC2") (pin "6") (pinfunction "/RST_6") (pintype "input"))
      (node (ref "LASER_DISX1") (pin "3") (pinfunction "JST3_3") (pintype "bidirectional"))
      (node (ref "LASER_DISX2") (pin "3") (pinfunction "JST3_3") (pintype "bidirectional"))
      (node (ref "LASER_DISX3") (pin "3") (pinfunction "JST3_3") (pintype "bidirectional"))
      (node (ref "LASER_DISX4") (pin "3") (pinfunction "JST3_3") (pintype "bidirectional"))
      (node (ref "LASER_DISX5") (pin "3") (pinfunction "JST3_3") (pintype "bidirectional"))
      (node (ref "LASER_DISX6") (pin "3") (pinfunction "JST3_3") (pintype "bidirectional"))
      (node (ref "LIMITSWITCH1") (pin "1") (pinfunction "JST1_1") (pintype "bidirectional"))
      (node (ref "LIMITSWITCH2") (pin "1") (pinfunction "JST1_1") (pintype "bidirectional"))
      (node (ref "R13") (pin "3") (pinfunction "1_3") (pintype "passive"))
      (node (ref "R14") (pin "2") (pinfunction "2_2") (pintype "passive"))
      (node (ref "R17") (pin "2") (pinfunction "2_2") (pintype "passive"))
      (node (ref "R4") (pin "1") (pinfunction "1_1") (pintype "passive"))
      (node (ref "R8") (pin "2") (pinfunction "2_2") (pintype "passive"))
      (node (ref "R9") (pin "1") (pinfunction "1_1") (pintype "passive"))
      (node (ref "U1") (pin "24") (pinfunction "VCC_24") (pintype "bidirectional"))
      (node (ref "U2") (pin "5") (pinfunction "OUT_5") (pintype "power_in"))
      (node (ref "X1") (pin "4") (pinfunction "SD_VDD_4") (pintype "power_in"))
      (node (ref "X2") (pin "2") (pinfunction "3.3V_2") (pintype "passive"))
    )
    (net (code "73") (name "unconnected-(IC1A-#RST-Pad9)") (class "Default")
      (node (ref "IC1") (pin "9") (pinfunction "#RST_9") (pintype "bidirectional"))
    )
    (net (code "74") (name "unconnected-(IC1A-#SUSPEND-Pad15)") (class "Default")
      (node (ref "IC1") (pin "15") (pinfunction "#SUSPEND_15") (pintype "output"))
    )
    (net (code "75") (name "unconnected-(IC1A-CTS-Pad18)") (class "Default")
      (node (ref "IC1") (pin "18") (pinfunction "CTS_18") (pintype "input"))
    )
    (net (code "76") (name "unconnected-(IC1A-DCD-Pad24)") (class "Default")
      (node (ref "IC1") (pin "24") (pinfunction "DCD_24") (pintype "input"))
    )
    (net (code "77") (name "unconnected-(IC1A-DSR-Pad22)") (class "Default")
      (node (ref "IC1") (pin "22") (pinfunction "DSR_22") (pintype "input"))
    )
    (net (code "78") (name "unconnected-(IC1A-GPIO0{slash}TXLED-Pad14)") (class "Default")
      (node (ref "IC1") (pin "14") (pinfunction "GPIO0/TXLED_14") (pintype "bidirectional"))
    )
    (net (code "79") (name "unconnected-(IC1A-GPIO1{slash}RXLED-Pad13)") (class "Default")
      (node (ref "IC1") (pin "13") (pinfunction "GPIO1/RXLED_13") (pintype "bidirectional"))
    )
    (net (code "80") (name "unconnected-(IC1A-GPIO2-Pad12)") (class "Default")
      (node (ref "IC1") (pin "12") (pinfunction "GPIO2_12") (pintype "bidirectional"))
    )
    (net (code "81") (name "unconnected-(IC1A-GPIO3-Pad11)") (class "Default")
      (node (ref "IC1") (pin "11") (pinfunction "GPIO3_11") (pintype "bidirectional"))
    )
    (net (code "82") (name "unconnected-(IC1A-NC-Pad10)") (class "Default")
      (node (ref "IC1") (pin "10") (pinfunction "NC_10") (pintype "no_connect"))
    )
    (net (code "83") (name "unconnected-(IC1A-RI-Pad1)") (class "Default")
      (node (ref "IC1") (pin "1") (pinfunction "RI_1") (pintype "input"))
    )
    (net (code "84") (name "unconnected-(IC1A-SUSPEND-Pad17)") (class "Default")
      (node (ref "IC1") (pin "17") (pinfunction "SUSPEND_17") (pintype "output"))
    )
    (net (code "85") (name "unconnected-(IC1A-VPP-Pad16)") (class "Default")
      (node (ref "IC1") (pin "16") (pinfunction "VPP_16") (pintype "bidirectional"))
    )
    (net (code "86") (name "unconnected-(IC2-INT-Pad8)") (class "Default")
      (node (ref "IC2") (pin "8") (pinfunction "INT_8") (pintype "output"))
    )
    (net (code "87") (name "unconnected-(U1-SCL6-Pad18)") (class "Default")
      (node (ref "U1") (pin "18") (pinfunction "SCL6_18") (pintype "bidirectional"))
    )
    (net (code "88") (name "unconnected-(U1-SCL7-Pad20)") (class "Default")
      (node (ref "U1") (pin "20") (pinfunction "SCL7_20") (pintype "bidirectional"))
    )
    (net (code "89") (name "unconnected-(U1-SDA6-Pad17)") (class "Default")
      (node (ref "U1") (pin "17") (pinfunction "SDA6_17") (pintype "bidirectional"))
    )
    (net (code "90") (name "unconnected-(U1-SDA7-Pad19)") (class "Default")
      (node (ref "U1") (pin "19") (pinfunction "SDA7_19") (pintype "bidirectional"))
    )
    (net (code "91") (name "unconnected-(U2-P4-Pad4)") (class "Default")
      (node (ref "U2") (pin "4") (pinfunction "P4_4") (pintype "bidirectional"))
    )
    (net (code "92") (name "unconnected-(X1-CARD_DETECT-PadCD1)") (class "Default")
      (node (ref "X1") (pin "CD1") (pinfunction "CARD_DETECT_CD1") (pintype "passive"))
    )
    (net (code "93") (name "unconnected-(X1-CARD_DETECT1-PadCD2)") (class "Default")
      (node (ref "X1") (pin "CD2") (pinfunction "CARD_DETECT1_CD2") (pintype "passive"))
    )
    (net (code "94") (name "unconnected-(X1-DAT1-Pad8)") (class "Default")
      (node (ref "X1") (pin "8") (pinfunction "DAT1_8") (pintype "bidirectional"))
    )
    (net (code "95") (name "unconnected-(X1-DAT2-Pad1)") (class "Default")
      (node (ref "X1") (pin "1") (pinfunction "DAT2_1") (pintype "bidirectional"))
    )
    (net (code "96") (name "unconnected-(X2-CLK-Pad20)") (class "Default")
      (node (ref "X2") (pin "20") (pinfunction "CLK_20") (pintype "bidirectional"))
    )
    (net (code "97") (name "unconnected-(X2-CMD-Pad19)") (class "Default")
      (node (ref "X2") (pin "19") (pinfunction "CMD_19") (pintype "bidirectional"))
    )
    (net (code "98") (name "unconnected-(X2-SD0-Pad21)") (class "Default")
      (node (ref "X2") (pin "21") (pinfunction "SD0_21") (pintype "bidirectional"))
    )
    (net (code "99") (name "unconnected-(X2-SD1-Pad22)") (class "Default")
      (node (ref "X2") (pin "22") (pinfunction "SD1_22") (pintype "bidirectional"))
    )
    (net (code "100") (name "unconnected-(X2-SD2-Pad17)") (class "Default")
      (node (ref "X2") (pin "17") (pinfunction "SD2_17") (pintype "bidirectional"))
    )
    (net (code "101") (name "unconnected-(X2-SD3-Pad18)") (class "Default")
      (node (ref "X2") (pin "18") (pinfunction "SD3_18") (pintype "bidirectional"))
    )
    (net (code "102") (name "unconnected-(X4-PadID)") (class "Default")
      (node (ref "X4") (pin "ID") (pinfunction "ID_ID") (pintype "bidirectional"))
    )
  )
)
